# OSO-MISC-20-014A_Neopixel_for_Spike.net
KiCad netlist of a schematic drawn in EAGLE
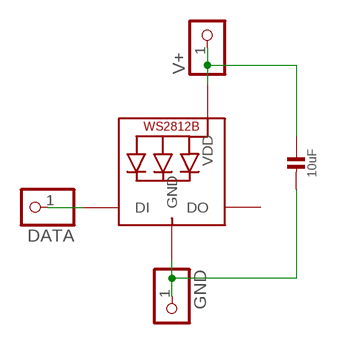
[diagram p0: schematic, sheet 1]

(export (version "E")
  (design (tool "Eeschema 10.0.6"))
  (components
    (comp (ref "C1")
      (value "10uF")
      (footprint "eagle-import:0805-NO")
      (libsource (lib "eagle-import") (part "CAP_CERAMIC0805-NOOUTLINE"))
    )
    (comp (ref "DATA")
      (value "PINHD-1X1")
      (footprint "eagle-import:1X01")
      (libsource (lib "eagle-import") (part "PINHD-1X1"))
    )
    (comp (ref "GND")
      (value "PINHD-1X1")
      (footprint "eagle-import:1X01")
      (libsource (lib "eagle-import") (part "PINHD-1X1"))
    )
    (comp (ref "LED1")
      (value "WS2812B3535")
      (footprint "eagle-import:LED3535")
      (libsource (lib "eagle-import") (part "WS2812B3535"))
    )
    (comp (ref "V+")
      (value "PINHD-1X1")
      (footprint "eagle-import:1X01")
      (libsource (lib "eagle-import") (part "PINHD-1X1"))
    )
  )
  (nets
    (net (code "1") (name "Net-(LED1-DI)") (class "Default")
      (node (ref "DATA") (pin "1") (pinfunction "1_1") (pintype "passive"))
      (node (ref "LED1") (pin "1") (pinfunction "DI_1") (pintype "input"))
    )
    (net (code "2") (name "Net-(LED1-GND)") (class "Default")
      (node (ref "C1") (pin "2") (pinfunction "2_2") (pintype "passive"))
      (node (ref "GND") (pin "1") (pinfunction "1_1") (pintype "passive"))
      (node (ref "LED1") (pin "4") (pinfunction "GND_4") (pintype "power_in"))
    )
    (net (code "3") (name "Net-(LED1-VDD)") (class "Default")
      (node (ref "C1") (pin "1") (pinfunction "1_1") (pintype "passive"))
      (node (ref "LED1") (pin "2") (pinfunction "VDD_2") (pintype "power_in"))
      (node (ref "V+") (pin "1") (pinfunction "1_1") (pintype "passive"))
    )
    (net (code "4") (name "unconnected-(LED1-DO-Pad3)") (class "Default")
      (node (ref "LED1") (pin "3") (pinfunction "DO_3") (pintype "output"))
    )
  )
)
